# CONNECTEUR_2.net
KiCad netlist of a schematic drawn in Altium Designer
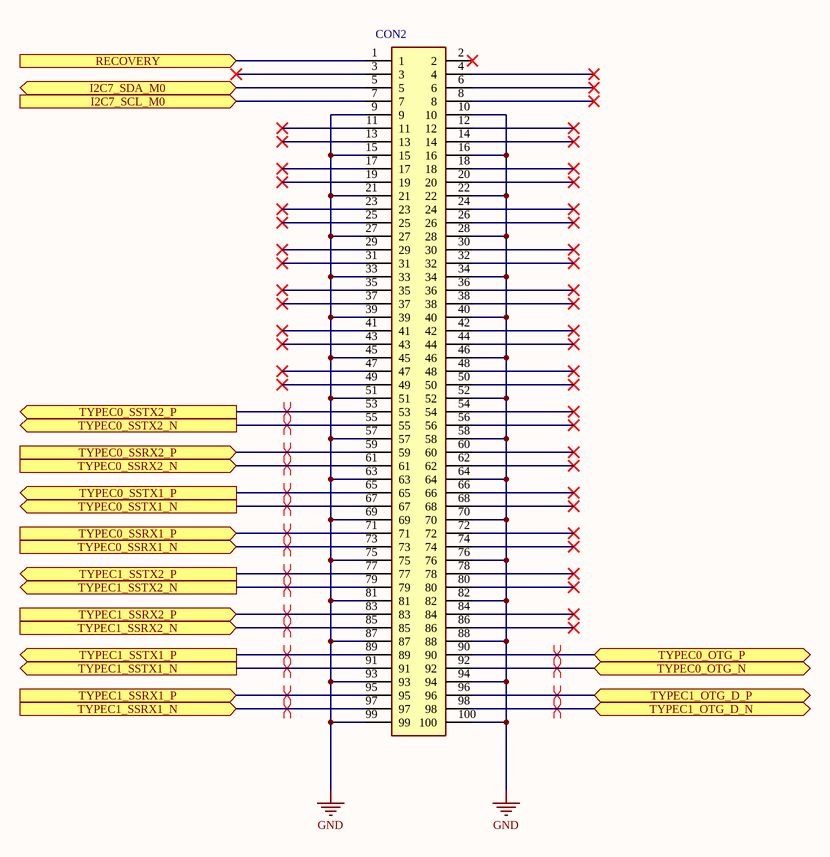
[diagram p0: CONNECTEUR_2.SchDoc]

(export (version "E")
  (design (tool "Eeschema 10.0.6"))
  (components
    (comp (ref "CON2")
      (value "DF40HC")
      (footprint "DF40HC30100DS04V51_MOD")
      (description "Stacking Board Connector, DF40 Series, Receptacle, 0.4 mm, 100, Surface Mount, G")
      (fields
        (field (name "MOUSER PART NUMBER") "798-DF40HC30100DS451")
        (field (name "ARROW PART NUMBER") "DF40HC(3.0)-100DS-0.4V(51")
      )
      (libsource (lib "DARKYDEN") (part "DF40HC(3.0)-100DS-0.4V(51)"))
    )
  )
  (nets
    (net (code "1") (name "/I2C7_SCL_M0") (class "Default")
      (node (ref "CON2") (pin "7") (pinfunction "7_7") (pintype "passive"))
    )
    (net (code "2") (name "/I2C7_SDA_M0") (class "Default")
      (node (ref "CON2") (pin "5") (pinfunction "5_5") (pintype "passive"))
    )
    (net (code "3") (name "/RECOVERY") (class "Default")
      (node (ref "CON2") (pin "1") (pinfunction "1_1") (pintype "passive"))
    )
    (net (code "4") (name "/TYPEC0_OTG_N") (class "Default")
      (node (ref "CON2") (pin "92") (pinfunction "92_92") (pintype "passive"))
    )
    (net (code "5") (name "/TYPEC0_OTG_P") (class "Default")
      (node (ref "CON2") (pin "90") (pinfunction "90_90") (pintype "passive"))
    )
    (net (code "6") (name "/TYPEC0_SSRX1_N") (class "Default")
      (node (ref "CON2") (pin "73") (pinfunction "73_73") (pintype "passive"))
    )
    (net (code "7") (name "/TYPEC0_SSRX1_P") (class "Default")
      (node (ref "CON2") (pin "71") (pinfunction "71_71") (pintype "passive"))
    )
    (net (code "8") (name "/TYPEC0_SSRX2_N") (class "Default")
      (node (ref "CON2") (pin "61") (pinfunction "61_61") (pintype "passive"))
    )
    (net (code "9") (name "/TYPEC0_SSRX2_P") (class "Default")
      (node (ref "CON2") (pin "59") (pinfunction "59_59") (pintype "passive"))
    )
    (net (code "10") (name "/TYPEC0_SSTX1_N") (class "Default")
      (node (ref "CON2") (pin "67") (pinfunction "67_67") (pintype "passive"))
    )
    (net (code "11") (name "/TYPEC0_SSTX1_P") (class "Default")
      (node (ref "CON2") (pin "65") (pinfunction "65_65") (pintype "passive"))
    )
    (net (code "12") (name "/TYPEC0_SSTX2_N") (class "Default")
      (node (ref "CON2") (pin "55") (pinfunction "55_55") (pintype "passive"))
    )
    (net (code "13") (name "/TYPEC0_SSTX2_P") (class "Default")
      (node (ref "CON2") (pin "53") (pinfunction "53_53") (pintype "passive"))
    )
    (net (code "14") (name "/TYPEC1_OTG_D_N") (class "Default")
      (node (ref "CON2") (pin "98") (pinfunction "98_98") (pintype "passive"))
    )
    (net (code "15") (name "/TYPEC1_OTG_D_P") (class "Default")
      (node (ref "CON2") (pin "96") (pinfunction "96_96") (pintype "passive"))
    )
    (net (code "16") (name "/TYPEC1_SSRX1_N") (class "Default")
      (node (ref "CON2") (pin "97") (pinfunction "97_97") (pintype "passive"))
    )
    (net (code "17") (name "/TYPEC1_SSRX1_P") (class "Default")
      (node (ref "CON2") (pin "95") (pinfunction "95_95") (pintype "passive"))
    )
    (net (code "18") (name "/TYPEC1_SSRX2_N") (class "Default")
      (node (ref "CON2") (pin "85") (pinfunction "85_85") (pintype "passive"))
    )
    (net (code "19") (name "/TYPEC1_SSRX2_P") (class "Default")
      (node (ref "CON2") (pin "83") (pinfunction "83_83") (pintype "passive"))
    )
    (net (code "20") (name "/TYPEC1_SSTX1_N") (class "Default")
      (node (ref "CON2") (pin "91") (pinfunction "91_91") (pintype "passive"))
    )
    (net (code "21") (name "/TYPEC1_SSTX1_P") (class "Default")
      (node (ref "CON2") (pin "89") (pinfunction "89_89") (pintype "passive"))
    )
    (net (code "22") (name "/TYPEC1_SSTX2_N") (class "Default")
      (node (ref "CON2") (pin "79") (pinfunction "79_79") (pintype "passive"))
    )
    (net (code "23") (name "/TYPEC1_SSTX2_P") (class "Default")
      (node (ref "CON2") (pin "77") (pinfunction "77_77") (pintype "passive"))
    )
    (net (code "24") (name "GND") (class "Default")
      (node (ref "CON2") (pin "10") (pinfunction "10_10") (pintype "passive"))
      (node (ref "CON2") (pin "100") (pinfunction "100_100") (pintype "passive"))
      (node (ref "CON2") (pin "15") (pinfunction "15_15") (pintype "passive"))
      (node (ref "CON2") (pin "16") (pinfunction "16_16") (pintype "passive"))
      (node (ref "CON2") (pin "21") (pinfunction "21_21") (pintype "passive"))
      (node (ref "CON2") (pin "22") (pinfunction "22_22") (pintype "passive"))
      (node (ref "CON2") (pin "27") (pinfunction "27_27") (pintype "passive"))
      (node (ref "CON2") (pin "28") (pinfunction "28_28") (pintype "passive"))
      (node (ref "CON2") (pin "33") (pinfunction "33_33") (pintype "passive"))
      (node (ref "CON2") (pin "34") (pinfunction "34_34") (pintype "passive"))
      (node (ref "CON2") (pin "39") (pinfunction "39_39") (pintype "passive"))
      (node (ref "CON2") (pin "40") (pinfunction "40_40") (pintype "passive"))
      (node (ref "CON2") (pin "45") (pinfunction "45_45") (pintype "passive"))
      (node (ref "CON2") (pin "46") (pinfunction "46_46") (pintype "passive"))
      (node (ref "CON2") (pin "51") (pinfunction "51_51") (pintype "passive"))
      (node (ref "CON2") (pin "52") (pinfunction "52_52") (pintype "passive"))
      (node (ref "CON2") (pin "57") (pinfunction "57_57") (pintype "passive"))
      (node (ref "CON2") (pin "58") (pinfunction "58_58") (pintype "passive"))
      (node (ref "CON2") (pin "63") (pinfunction "63_63") (pintype "passive"))
      (node (ref "CON2") (pin "64") (pinfunction "64_64") (pintype "passive"))
      (node (ref "CON2") (pin "69") (pinfunction "69_69") (pintype "passive"))
      (node (ref "CON2") (pin "70") (pinfunction "70_70") (pintype "passive"))
      (node (ref "CON2") (pin "75") (pinfunction "75_75") (pintype "passive"))
      (node (ref "CON2") (pin "76") (pinfunction "76_76") (pintype "passive"))
      (node (ref "CON2") (pin "81") (pinfunction "81_81") (pintype "passive"))
      (node (ref "CON2") (pin "82") (pinfunction "82_82") (pintype "passive"))
      (node (ref "CON2") (pin "87") (pinfunction "87_87") (pintype "passive"))
      (node (ref "CON2") (pin "88") (pinfunction "88_88") (pintype "passive"))
      (node (ref "CON2") (pin "9") (pinfunction "9_9") (pintype "passive"))
      (node (ref "CON2") (pin "93") (pinfunction "93_93") (pintype "passive"))
      (node (ref "CON2") (pin "94") (pinfunction "94_94") (pintype "passive"))
      (node (ref "CON2") (pin "99") (pinfunction "99_99") (pintype "passive"))
    )
    (net (code "25") (name "unconnected-(CON2-Pad2)") (class "Default")
      (node (ref "CON2") (pin "2") (pinfunction "2_2") (pintype "passive+no_connect"))
    )
    (net (code "26") (name "unconnected-(CON2-Pad3)") (class "Default")
      (node (ref "CON2") (pin "3") (pinfunction "3_3") (pintype "passive+no_connect"))
    )
    (net (code "27") (name "unconnected-(CON2-Pad4)") (class "Default")
      (node (ref "CON2") (pin "4") (pinfunction "4_4") (pintype "passive+no_connect"))
    )
    (net (code "28") (name "unconnected-(CON2-Pad6)") (class "Default")
      (node (ref "CON2") (pin "6") (pinfunction "6_6") (pintype "passive+no_connect"))
    )
    (net (code "29") (name "unconnected-(CON2-Pad8)") (class "Default")
      (node (ref "CON2") (pin "8") (pinfunction "8_8") (pintype "passive+no_connect"))
    )
    (net (code "30") (name "unconnected-(CON2-Pad11)") (class "Default")
      (node (ref "CON2") (pin "11") (pinfunction "11_11") (pintype "passive+no_connect"))
    )
    (net (code "31") (name "unconnected-(CON2-Pad12)") (class "Default")
      (node (ref "CON2") (pin "12") (pinfunction "12_12") (pintype "passive+no_connect"))
    )
    (net (code "32") (name "unconnected-(CON2-Pad13)") (class "Default")
      (node (ref "CON2") (pin "13") (pinfunction "13_13") (pintype "passive+no_connect"))
    )
    (net (code "33") (name "unconnected-(CON2-Pad14)") (class "Default")
      (node (ref "CON2") (pin "14") (pinfunction "14_14") (pintype "passive+no_connect"))
    )
    (net (code "34") (name "unconnected-(CON2-Pad17)") (class "Default")
      (node (ref "CON2") (pin "17") (pinfunction "17_17") (pintype "passive+no_connect"))
    )
    (net (code "35") (name "unconnected-(CON2-Pad18)") (class "Default")
      (node (ref "CON2") (pin "18") (pinfunction "18_18") (pintype "passive+no_connect"))
    )
    (net (code "36") (name "unconnected-(CON2-Pad19)") (class "Default")
      (node (ref "CON2") (pin "19") (pinfunction "19_19") (pintype "passive+no_connect"))
    )
    (net (code "37") (name "unconnected-(CON2-Pad20)") (class "Default")
      (node (ref "CON2") (pin "20") (pinfunction "20_20") (pintype "passive+no_connect"))
    )
    (net (code "38") (name "unconnected-(CON2-Pad23)") (class "Default")
      (node (ref "CON2") (pin "23") (pinfunction "23_23") (pintype "passive+no_connect"))
    )
    (net (code "39") (name "unconnected-(CON2-Pad24)") (class "Default")
      (node (ref "CON2") (pin "24") (pinfunction "24_24") (pintype "passive+no_connect"))
    )
    (net (code "40") (name "unconnected-(CON2-Pad25)") (class "Default")
      (node (ref "CON2") (pin "25") (pinfunction "25_25") (pintype "passive+no_connect"))
    )
    (net (code "41") (name "unconnected-(CON2-Pad26)") (class "Default")
      (node (ref "CON2") (pin "26") (pinfunction "26_26") (pintype "passive+no_connect"))
    )
    (net (code "42") (name "unconnected-(CON2-Pad29)") (class "Default")
      (node (ref "CON2") (pin "29") (pinfunction "29_29") (pintype "passive+no_connect"))
    )
    (net (code "43") (name "unconnected-(CON2-Pad30)") (class "Default")
      (node (ref "CON2") (pin "30") (pinfunction "30_30") (pintype "passive+no_connect"))
    )
    (net (code "44") (name "unconnected-(CON2-Pad31)") (class "Default")
      (node (ref "CON2") (pin "31") (pinfunction "31_31") (pintype "passive+no_connect"))
    )
    (net (code "45") (name "unconnected-(CON2-Pad32)") (class "Default")
      (node (ref "CON2") (pin "32") (pinfunction "32_32") (pintype "passive+no_connect"))
    )
    (net (code "46") (name "unconnected-(CON2-Pad35)") (class "Default")
      (node (ref "CON2") (pin "35") (pinfunction "35_35") (pintype "passive+no_connect"))
    )
    (net (code "47") (name "unconnected-(CON2-Pad36)") (class "Default")
      (node (ref "CON2") (pin "36") (pinfunction "36_36") (pintype "passive+no_connect"))
    )
    (net (code "48") (name "unconnected-(CON2-Pad37)") (class "Default")
      (node (ref "CON2") (pin "37") (pinfunction "37_37") (pintype "passive+no_connect"))
    )
    (net (code "49") (name "unconnected-(CON2-Pad38)") (class "Default")
      (node (ref "CON2") (pin "38") (pinfunction "38_38") (pintype "passive+no_connect"))
    )
    (net (code "50") (name "unconnected-(CON2-Pad41)") (class "Default")
      (node (ref "CON2") (pin "41") (pinfunction "41_41") (pintype "passive+no_connect"))
    )
    (net (code "51") (name "unconnected-(CON2-Pad42)") (class "Default")
      (node (ref "CON2") (pin "42") (pinfunction "42_42") (pintype "passive+no_connect"))
    )
    (net (code "52") (name "unconnected-(CON2-Pad43)") (class "Default")
      (node (ref "CON2") (pin "43") (pinfunction "43_43") (pintype "passive+no_connect"))
    )
    (net (code "53") (name "unconnected-(CON2-Pad44)") (class "Default")
      (node (ref "CON2") (pin "44") (pinfunction "44_44") (pintype "passive+no_connect"))
    )
    (net (code "54") (name "unconnected-(CON2-Pad47)") (class "Default")
      (node (ref "CON2") (pin "47") (pinfunction "47_47") (pintype "passive+no_connect"))
    )
    (net (code "55") (name "unconnected-(CON2-Pad48)") (class "Default")
      (node (ref "CON2") (pin "48") (pinfunction "48_48") (pintype "passive+no_connect"))
    )
    (net (code "56") (name "unconnected-(CON2-Pad49)") (class "Default")
      (node (ref "CON2") (pin "49") (pinfunction "49_49") (pintype "passive+no_connect"))
    )
    (net (code "57") (name "unconnected-(CON2-Pad50)") (class "Default")
      (node (ref "CON2") (pin "50") (pinfunction "50_50") (pintype "passive+no_connect"))
    )
    (net (code "58") (name "unconnected-(CON2-Pad54)") (class "Default")
      (node (ref "CON2") (pin "54") (pinfunction "54_54") (pintype "passive+no_connect"))
    )
    (net (code "59") (name "unconnected-(CON2-Pad56)") (class "Default")
      (node (ref "CON2") (pin "56") (pinfunction "56_56") (pintype "passive+no_connect"))
    )
    (net (code "60") (name "unconnected-(CON2-Pad60)") (class "Default")
      (node (ref "CON2") (pin "60") (pinfunction "60_60") (pintype "passive+no_connect"))
    )
    (net (code "61") (name "unconnected-(CON2-Pad62)") (class "Default")
      (node (ref "CON2") (pin "62") (pinfunction "62_62") (pintype "passive+no_connect"))
    )
    (net (code "62") (name "unconnected-(CON2-Pad66)") (class "Default")
      (node (ref "CON2") (pin "66") (pinfunction "66_66") (pintype "passive+no_connect"))
    )
    (net (code "63") (name "unconnected-(CON2-Pad68)") (class "Default")
      (node (ref "CON2") (pin "68") (pinfunction "68_68") (pintype "passive+no_connect"))
    )
    (net (code "64") (name "unconnected-(CON2-Pad72)") (class "Default")
      (node (ref "CON2") (pin "72") (pinfunction "72_72") (pintype "passive+no_connect"))
    )
    (net (code "65") (name "unconnected-(CON2-Pad74)") (class "Default")
      (node (ref "CON2") (pin "74") (pinfunction "74_74") (pintype "passive+no_connect"))
    )
    (net (code "66") (name "unconnected-(CON2-Pad78)") (class "Default")
      (node (ref "CON2") (pin "78") (pinfunction "78_78") (pintype "passive+no_connect"))
    )
    (net (code "67") (name "unconnected-(CON2-Pad80)") (class "Default")
      (node (ref "CON2") (pin "80") (pinfunction "80_80") (pintype "passive+no_connect"))
    )
    (net (code "68") (name "unconnected-(CON2-Pad84)") (class "Default")
      (node (ref "CON2") (pin "84") (pinfunction "84_84") (pintype "passive+no_connect"))
    )
    (net (code "69") (name "unconnected-(CON2-Pad86)") (class "Default")
      (node (ref "CON2") (pin "86") (pinfunction "86_86") (pintype "passive+no_connect"))
    )
  )
)
